# CONTROL_circuit_LED_for_Junction_Box.net
KiCad netlist of a schematic drawn in EAGLE
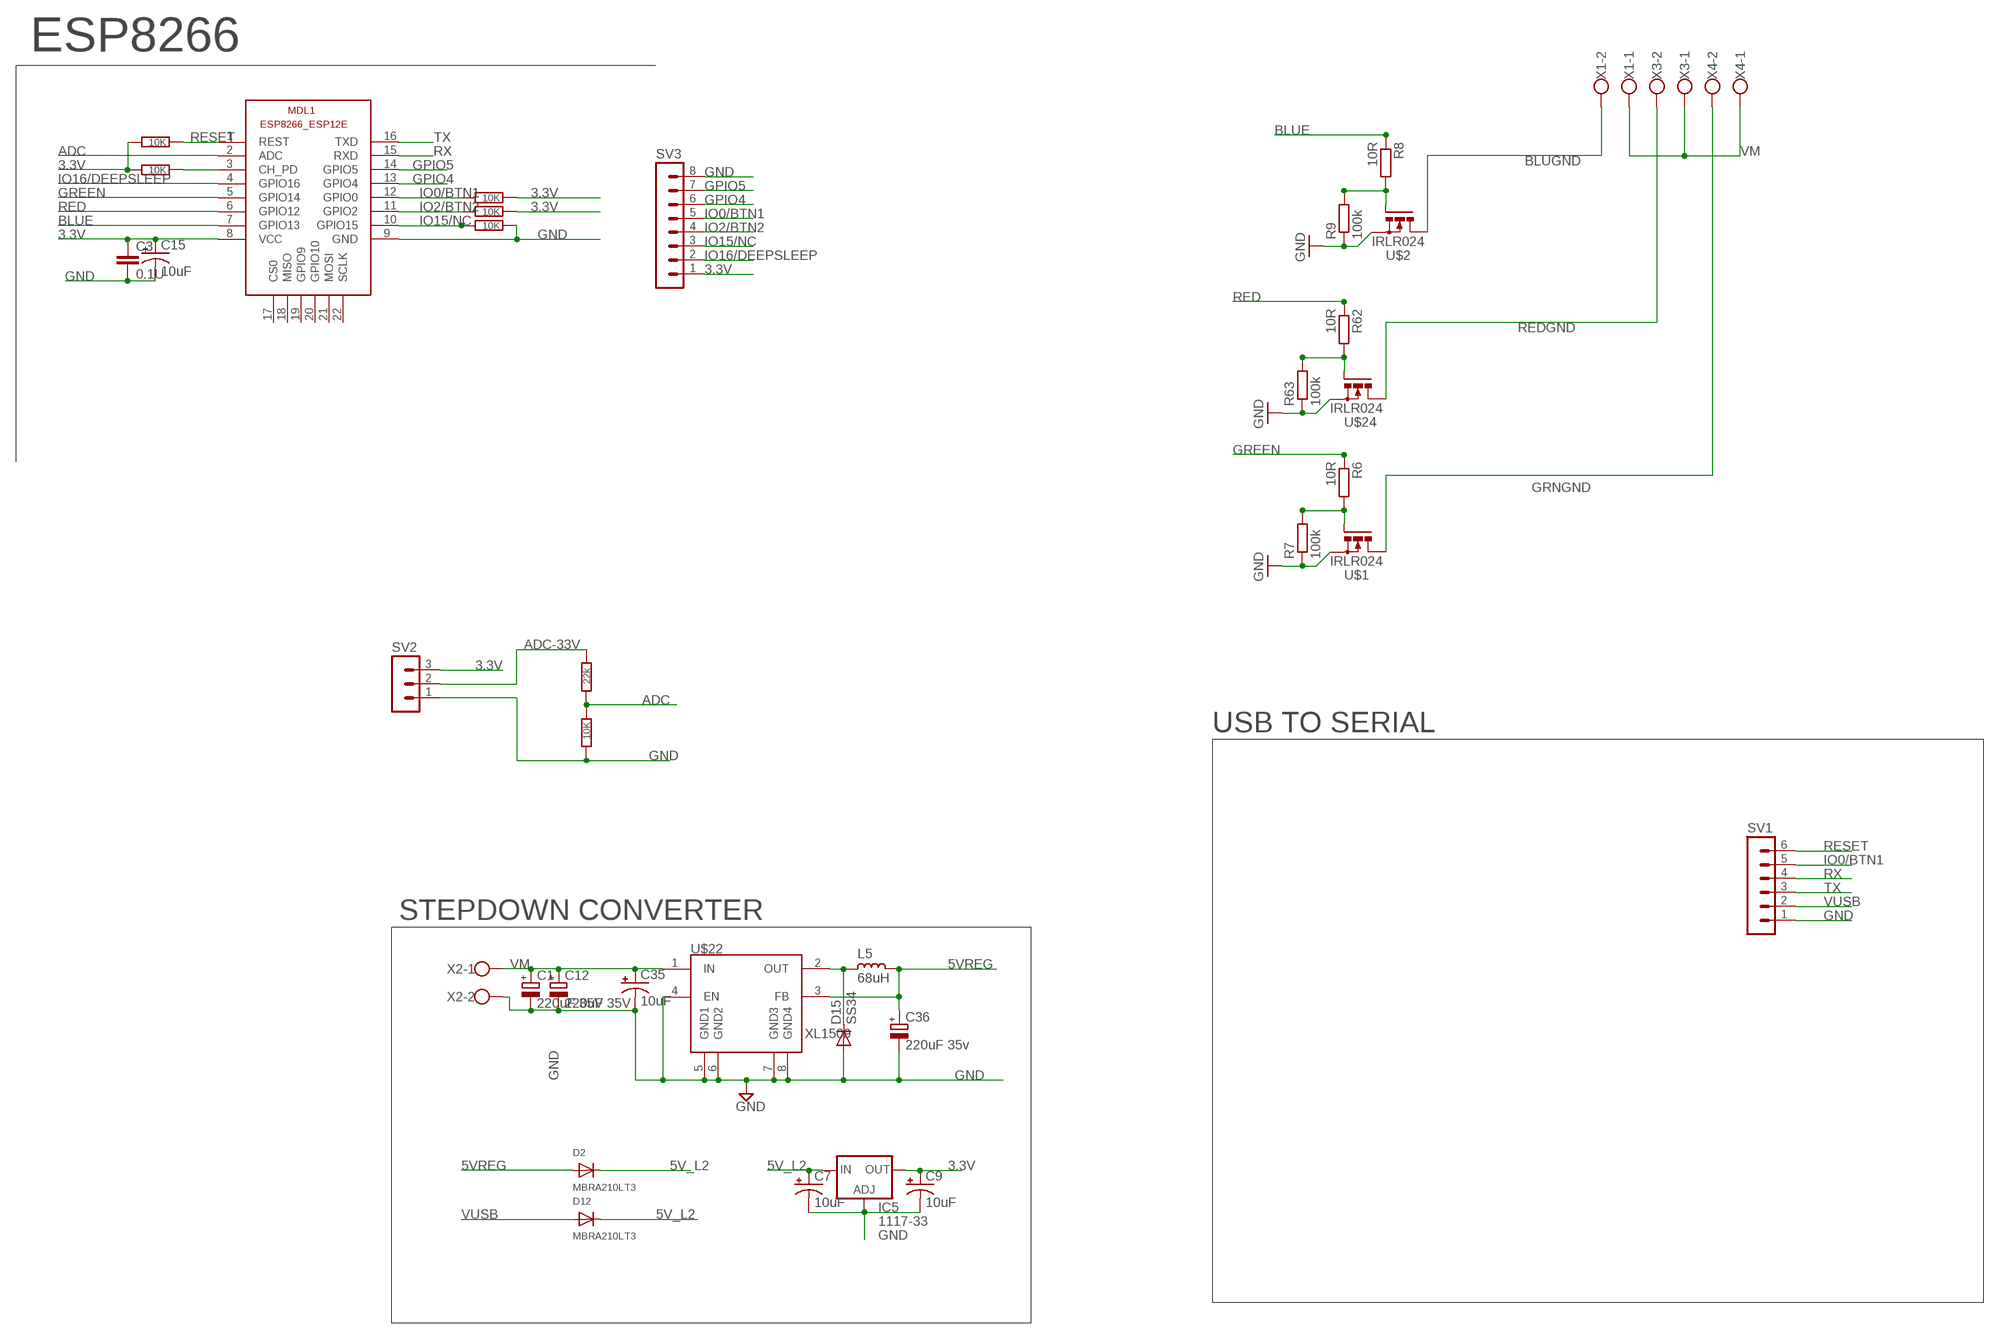
[diagram p0: schematic, sheet 1]

(export (version "E")
  (design (tool "Eeschema 10.0.6"))
  (components
    (comp (ref "C1")
      (value "220uF 35V")
      (footprint "eagle-import:E3,5-8")
      (libsource (lib "eagle-import") (part "CPOL-EUE3.5-8"))
    )
    (comp (ref "C3")
      (value "0.1U")
      (footprint "eagle-import:C1206")
      (libsource (lib "eagle-import") (part "C-EUC1206"))
    )
    (comp (ref "C7")
      (value "10uF")
      (footprint "eagle-import:EIA3216")
      (libsource (lib "eagle-import") (part "CAP_POL1206"))
    )
    (comp (ref "C9")
      (value "10uF")
      (footprint "eagle-import:EIA3216")
      (libsource (lib "eagle-import") (part "CAP_POL1206"))
    )
    (comp (ref "C12")
      (value "220uF 35V")
      (footprint "eagle-import:E3,5-8")
      (libsource (lib "eagle-import") (part "CPOL-EUE3.5-8"))
    )
    (comp (ref "C15")
      (value "10uF")
      (footprint "eagle-import:EIA3216")
      (libsource (lib "eagle-import") (part "CAP_POL1206"))
    )
    (comp (ref "C35")
      (value "10uF")
      (footprint "eagle-import:EIA3216")
      (libsource (lib "eagle-import") (part "CAP_POL1206"))
    )
    (comp (ref "C36")
      (value "220uF 35v")
      (footprint "eagle-import:E3,5-8")
      (libsource (lib "eagle-import") (part "CPOL-EUE3.5-8"))
    )
    (comp (ref "D2")
      (value "MBRA210LT3")
      (footprint "eagle-import:SMADIODE")
      (libsource (lib "eagle-import") (part "DIODESMA"))
    )
    (comp (ref "D12")
      (value "MBRA210LT3")
      (footprint "eagle-import:SMADIODE")
      (libsource (lib "eagle-import") (part "DIODESMA"))
    )
    (comp (ref "D15")
      (value "SS34")
      (footprint "eagle-import:DO-214AC")
      (libsource (lib "eagle-import") (part "DIODE-DO-214AC"))
    )
    (comp (ref "IC5")
      (value "1117-33")
      (footprint "eagle-import:SOT223")
      (libsource (lib "eagle-import") (part "LD117A?S33TR"))
    )
    (comp (ref "L5")
      (value "68uH")
      (footprint "eagle-import:CD75")
      (libsource (lib "eagle-import") (part "L_CD75"))
    )
    (comp (ref "MDL1")
      (value "ESP8266-12EESP8266-ESP12E")
      (footprint "eagle-import:ESP8266-ESP12E")
      (libsource (lib "eagle-import") (part "ESP8266-12EESP8266-ESP12E"))
    )
    (comp (ref "R3")
      (value "22k")
      (footprint "eagle-import:R1206")
      (libsource (lib "eagle-import") (part "R-EU_R1206"))
    )
    (comp (ref "R4")
      (value "10K")
      (footprint "eagle-import:R1206")
      (libsource (lib "eagle-import") (part "R-EU_R1206"))
    )
    (comp (ref "R6")
      (value "10R")
      (footprint "eagle-import:R1206")
      (libsource (lib "eagle-import") (part "resistor_R-EU_R1206"))
    )
    (comp (ref "R7")
      (value "100k")
      (footprint "eagle-import:R1206")
      (libsource (lib "eagle-import") (part "resistor_R-EU_R1206"))
    )
    (comp (ref "R8")
      (value "10R")
      (footprint "eagle-import:R1206")
      (libsource (lib "eagle-import") (part "resistor_R-EU_R1206"))
    )
    (comp (ref "R9")
      (value "100k")
      (footprint "eagle-import:R1206")
      (libsource (lib "eagle-import") (part "resistor_R-EU_R1206"))
    )
    (comp (ref "R11")
      (value "10K")
      (footprint "eagle-import:R1206")
      (libsource (lib "eagle-import") (part "R-EU_R1206"))
    )
    (comp (ref "R12")
      (value "10K")
      (footprint "eagle-import:R1206")
      (libsource (lib "eagle-import") (part "R-EU_R1206"))
    )
    (comp (ref "R28")
      (value "10K")
      (footprint "eagle-import:R1206")
      (libsource (lib "eagle-import") (part "R-EU_R1206"))
    )
    (comp (ref "R29")
      (value "10K")
      (footprint "eagle-import:R1206")
      (libsource (lib "eagle-import") (part "R-EU_R1206"))
    )
    (comp (ref "R31")
      (value "10K")
      (footprint "eagle-import:R1206")
      (libsource (lib "eagle-import") (part "R-EU_R1206"))
    )
    (comp (ref "R62")
      (value "10R")
      (footprint "eagle-import:R1206")
      (libsource (lib "eagle-import") (part "resistor_R-EU_R1206"))
    )
    (comp (ref "R63")
      (value "100k")
      (footprint "eagle-import:R1206")
      (libsource (lib "eagle-import") (part "resistor_R-EU_R1206"))
    )
    (comp (ref "SV1")
      (value "MA06-1")
      (footprint "eagle-import:MA06-1")
      (libsource (lib "eagle-import") (part "MA06-1"))
    )
    (comp (ref "SV2")
      (value "MA03-1")
      (footprint "eagle-import:MA03-1")
      (libsource (lib "eagle-import") (part "MA03-1"))
    )
    (comp (ref "SV3")
      (value "MA08-1")
      (footprint "eagle-import:MA08-1")
      (libsource (lib "eagle-import") (part "MA08-1"))
    )
    (comp (ref "U$1")
      (value "IRLR024")
      (footprint "eagle-import:D-PAK_TO252AA")
      (libsource (lib "eagle-import") (part "N-POWER-MOSFETDPAK-MOSFET"))
    )
    (comp (ref "U$2")
      (value "IRLR024")
      (footprint "eagle-import:D-PAK_TO252AA")
      (libsource (lib "eagle-import") (part "N-POWER-MOSFETDPAK-MOSFET"))
    )
    (comp (ref "U$22")
      (value "XL1509")
      (footprint "eagle-import:SO08")
      (libsource (lib "eagle-import") (part "XL1509"))
    )
    (comp (ref "U$24")
      (value "IRLR024")
      (footprint "eagle-import:D-PAK_TO252AA")
      (libsource (lib "eagle-import") (part "N-POWER-MOSFETDPAK-MOSFET"))
    )
    (comp (ref "X1")
      (value "W237-102")
      (footprint "eagle-import:W237-102")
      (fields (field (name "MPN") "237-102"))
      (libsource (lib "eagle-import") (part "W237-102"))
    )
    (comp (ref "X2")
      (value "W237-102")
      (footprint "eagle-import:W237-102")
      (fields (field (name "MPN") "237-102"))
      (libsource (lib "eagle-import") (part "W237-102"))
    )
    (comp (ref "X3")
      (value "W237-102")
      (footprint "eagle-import:W237-102")
      (fields (field (name "MPN") "237-102"))
      (libsource (lib "eagle-import") (part "W237-102"))
    )
    (comp (ref "X4")
      (value "W237-102")
      (footprint "eagle-import:W237-102")
      (fields (field (name "MPN") "237-102"))
      (libsource (lib "eagle-import") (part "W237-102"))
    )
  )
  (nets
    (net (code "1") (name "/3.3V") (class "Default")
      (node (ref "C15") (pin "A") (pinfunction "+_A") (pintype "passive"))
      (node (ref "C3") (pin "1") (pinfunction "1_1") (pintype "passive"))
      (node (ref "C9") (pin "A") (pinfunction "+_A") (pintype "passive"))
      (node (ref "IC5") (pin "4") (pinfunction "OUT_4") (pintype "passive"))
      (node (ref "MDL1") (pin "8") (pinfunction "VCC_8") (pintype "bidirectional"))
      (node (ref "R11") (pin "2") (pinfunction "2_2") (pintype "passive"))
      (node (ref "R12") (pin "2") (pinfunction "2_2") (pintype "passive"))
      (node (ref "R28") (pin "1") (pinfunction "1_1") (pintype "passive"))
      (node (ref "R29") (pin "1") (pinfunction "1_1") (pintype "passive"))
      (node (ref "SV2") (pin "3") (pinfunction "3_3") (pintype "passive"))
      (node (ref "SV3") (pin "1") (pinfunction "1_1") (pintype "passive"))
    )
    (net (code "2") (name "/5VREG") (class "Default")
      (node (ref "C36") (pin "+") (pinfunction "+_+") (pintype "passive"))
      (node (ref "D2") (pin "A") (pinfunction "A_A") (pintype "passive"))
      (node (ref "L5") (pin "1") (pinfunction "1_1") (pintype "passive"))
      (node (ref "U$22") (pin "3") (pinfunction "FB_3") (pintype "bidirectional"))
    )
    (net (code "3") (name "/5V_L2") (class "Default")
      (node (ref "C7") (pin "A") (pinfunction "+_A") (pintype "passive"))
      (node (ref "D12") (pin "C") (pinfunction "C_C") (pintype "passive"))
      (node (ref "D2") (pin "C") (pinfunction "C_C") (pintype "passive"))
      (node (ref "IC5") (pin "3") (pinfunction "IN_3") (pintype "input"))
    )
    (net (code "4") (name "/ADC") (class "Default")
      (node (ref "MDL1") (pin "2") (pinfunction "ADC_2") (pintype "bidirectional"))
      (node (ref "R3") (pin "1") (pinfunction "1_1") (pintype "passive"))
      (node (ref "R4") (pin "2") (pinfunction "2_2") (pintype "passive"))
    )
    (net (code "5") (name "/ADC-33V") (class "Default")
      (node (ref "R3") (pin "2") (pinfunction "2_2") (pintype "passive"))
      (node (ref "SV2") (pin "2") (pinfunction "2_2") (pintype "passive"))
    )
    (net (code "6") (name "/BLUE") (class "Default")
      (node (ref "MDL1") (pin "7") (pinfunction "GPIO13_7") (pintype "bidirectional"))
      (node (ref "R8") (pin "1") (pinfunction "1_1") (pintype "passive"))
    )
    (net (code "7") (name "/BLUGND") (class "Default")
      (node (ref "U$2") (pin "4") (pinfunction "D_4") (pintype "passive"))
      (node (ref "X1") (pin "2") (pinfunction "KL_2") (pintype "passive"))
    )
    (net (code "8") (name "/GPIO4") (class "Default")
      (node (ref "MDL1") (pin "13") (pinfunction "GPIO4_13") (pintype "bidirectional"))
      (node (ref "SV3") (pin "6") (pinfunction "6_6") (pintype "passive"))
    )
    (net (code "9") (name "/GPIO5") (class "Default")
      (node (ref "MDL1") (pin "14") (pinfunction "GPIO5_14") (pintype "bidirectional"))
      (node (ref "SV3") (pin "7") (pinfunction "7_7") (pintype "passive"))
    )
    (net (code "10") (name "/GREEN") (class "Default")
      (node (ref "MDL1") (pin "5") (pinfunction "GPIO14_5") (pintype "bidirectional"))
      (node (ref "R6") (pin "1") (pinfunction "1_1") (pintype "passive"))
    )
    (net (code "11") (name "/GRNGND") (class "Default")
      (node (ref "U$1") (pin "4") (pinfunction "D_4") (pintype "passive"))
      (node (ref "X4") (pin "2") (pinfunction "KL_2") (pintype "passive"))
    )
    (net (code "12") (name "/IO0{slash}BTN1") (class "Default")
      (node (ref "MDL1") (pin "12") (pinfunction "GPIO0_12") (pintype "bidirectional"))
      (node (ref "R12") (pin "1") (pinfunction "1_1") (pintype "passive"))
      (node (ref "SV1") (pin "5") (pinfunction "5_5") (pintype "passive"))
      (node (ref "SV3") (pin "5") (pinfunction "5_5") (pintype "passive"))
    )
    (net (code "13") (name "/IO2{slash}BTN2") (class "Default")
      (node (ref "MDL1") (pin "11") (pinfunction "GPIO2_11") (pintype "bidirectional"))
      (node (ref "R11") (pin "1") (pinfunction "1_1") (pintype "passive"))
      (node (ref "SV3") (pin "4") (pinfunction "4_4") (pintype "passive"))
    )
    (net (code "14") (name "/IO15{slash}NC") (class "Default")
      (node (ref "MDL1") (pin "10") (pinfunction "GPIO15_10") (pintype "bidirectional"))
      (node (ref "R31") (pin "1") (pinfunction "1_1") (pintype "passive"))
      (node (ref "SV3") (pin "3") (pinfunction "3_3") (pintype "passive"))
    )
    (net (code "15") (name "/IO16{slash}DEEPSLEEP") (class "Default")
      (node (ref "MDL1") (pin "4") (pinfunction "GPIO16_4") (pintype "bidirectional"))
      (node (ref "SV3") (pin "2") (pinfunction "2_2") (pintype "passive"))
    )
    (net (code "16") (name "/RED") (class "Default")
      (node (ref "MDL1") (pin "6") (pinfunction "GPIO12_6") (pintype "bidirectional"))
      (node (ref "R62") (pin "1") (pinfunction "1_1") (pintype "passive"))
    )
    (net (code "17") (name "/REDGND") (class "Default")
      (node (ref "U$24") (pin "4") (pinfunction "D_4") (pintype "passive"))
      (node (ref "X3") (pin "2") (pinfunction "KL_2") (pintype "passive"))
    )
    (net (code "18") (name "/RESET") (class "Default")
      (node (ref "MDL1") (pin "1") (pinfunction "REST_1") (pintype "bidirectional"))
      (node (ref "R29") (pin "2") (pinfunction "2_2") (pintype "passive"))
      (node (ref "SV1") (pin "6") (pinfunction "6_6") (pintype "passive"))
    )
    (net (code "19") (name "/RX") (class "Default")
      (node (ref "MDL1") (pin "15") (pinfunction "RXD_15") (pintype "bidirectional"))
      (node (ref "SV1") (pin "4") (pinfunction "4_4") (pintype "passive"))
    )
    (net (code "20") (name "/TX") (class "Default")
      (node (ref "MDL1") (pin "16") (pinfunction "TXD_16") (pintype "bidirectional"))
      (node (ref "SV1") (pin "3") (pinfunction "3_3") (pintype "passive"))
    )
    (net (code "21") (name "/VM") (class "Default")
      (node (ref "C1") (pin "+") (pinfunction "+_+") (pintype "passive"))
      (node (ref "C12") (pin "+") (pinfunction "+_+") (pintype "passive"))
      (node (ref "C35") (pin "A") (pinfunction "+_A") (pintype "passive"))
      (node (ref "U$22") (pin "1") (pinfunction "IN_1") (pintype "bidirectional"))
      (node (ref "X1") (pin "1") (pinfunction "KL_1") (pintype "passive"))
      (node (ref "X2") (pin "1") (pinfunction "KL_1") (pintype "passive"))
      (node (ref "X3") (pin "1") (pinfunction "KL_1") (pintype "passive"))
      (node (ref "X4") (pin "1") (pinfunction "KL_1") (pintype "passive"))
    )
    (net (code "22") (name "/VUSB") (class "Default")
      (node (ref "D12") (pin "A") (pinfunction "A_A") (pintype "passive"))
      (node (ref "SV1") (pin "2") (pinfunction "2_2") (pintype "passive"))
    )
    (net (code "23") (name "GND") (class "Default")
      (node (ref "C1") (pin "-") (pinfunction "-_-") (pintype "passive"))
      (node (ref "C12") (pin "-") (pinfunction "-_-") (pintype "passive"))
      (node (ref "C15") (pin "C") (pinfunction "-_C") (pintype "passive"))
      (node (ref "C3") (pin "2") (pinfunction "2_2") (pintype "passive"))
      (node (ref "C35") (pin "C") (pinfunction "-_C") (pintype "passive"))
      (node (ref "C36") (pin "-") (pinfunction "-_-") (pintype "passive"))
      (node (ref "C7") (pin "C") (pinfunction "-_C") (pintype "passive"))
      (node (ref "C9") (pin "C") (pinfunction "-_C") (pintype "passive"))
      (node (ref "D15") (pin "2") (pinfunction "A_2") (pintype "passive"))
      (node (ref "IC5") (pin "1") (pinfunction "ADJ_1") (pintype "input"))
      (node (ref "MDL1") (pin "9") (pinfunction "GND_9") (pintype "bidirectional"))
      (node (ref "R31") (pin "2") (pinfunction "2_2") (pintype "passive"))
      (node (ref "R4") (pin "1") (pinfunction "1_1") (pintype "passive"))
      (node (ref "R63") (pin "1") (pinfunction "1_1") (pintype "passive"))
      (node (ref "R7") (pin "1") (pinfunction "1_1") (pintype "passive"))
      (node (ref "R9") (pin "1") (pinfunction "1_1") (pintype "passive"))
      (node (ref "SV1") (pin "1") (pinfunction "1_1") (pintype "passive"))
      (node (ref "SV2") (pin "1") (pinfunction "1_1") (pintype "passive"))
      (node (ref "SV3") (pin "8") (pinfunction "8_8") (pintype "passive"))
      (node (ref "U$1") (pin "3") (pinfunction "S_3") (pintype "passive"))
      (node (ref "U$2") (pin "3") (pinfunction "S_3") (pintype "passive"))
      (node (ref "U$22") (pin "4") (pinfunction "EN_4") (pintype "bidirectional"))
      (node (ref "U$22") (pin "5") (pinfunction "GND1_5") (pintype "bidirectional"))
      (node (ref "U$22") (pin "6") (pinfunction "GND2_6") (pintype "bidirectional"))
      (node (ref "U$22") (pin "7") (pinfunction "GND3_7") (pintype "bidirectional"))
      (node (ref "U$22") (pin "8") (pinfunction "GND4_8") (pintype "bidirectional"))
      (node (ref "U$24") (pin "3") (pinfunction "S_3") (pintype "passive"))
      (node (ref "X2") (pin "2") (pinfunction "KL_2") (pintype "passive"))
    )
    (net (code "24") (name "Net-(D15-C)") (class "Default")
      (node (ref "D15") (pin "1") (pinfunction "C_1") (pintype "passive"))
      (node (ref "L5") (pin "2") (pinfunction "2_2") (pintype "passive"))
      (node (ref "U$22") (pin "2") (pinfunction "OUT_2") (pintype "bidirectional"))
    )
    (net (code "25") (name "Net-(MDL1-CH_PD)") (class "Default")
      (node (ref "MDL1") (pin "3") (pinfunction "CH_PD_3") (pintype "bidirectional"))
      (node (ref "R28") (pin "2") (pinfunction "2_2") (pintype "passive"))
    )
    (net (code "26") (name "Net-(U$1-G)") (class "Default")
      (node (ref "R6") (pin "2") (pinfunction "2_2") (pintype "passive"))
      (node (ref "R7") (pin "2") (pinfunction "2_2") (pintype "passive"))
      (node (ref "U$1") (pin "1") (pinfunction "G_1") (pintype "passive"))
    )
    (net (code "27") (name "Net-(U$2-G)") (class "Default")
      (node (ref "R8") (pin "2") (pinfunction "2_2") (pintype "passive"))
      (node (ref "R9") (pin "2") (pinfunction "2_2") (pintype "passive"))
      (node (ref "U$2") (pin "1") (pinfunction "G_1") (pintype "passive"))
    )
    (net (code "28") (name "Net-(U$24-G)") (class "Default")
      (node (ref "R62") (pin "2") (pinfunction "2_2") (pintype "passive"))
      (node (ref "R63") (pin "2") (pinfunction "2_2") (pintype "passive"))
      (node (ref "U$24") (pin "1") (pinfunction "G_1") (pintype "passive"))
    )
    (net (code "29") (name "unconnected-(MDL1-CS0-Pad17)") (class "Default")
      (node (ref "MDL1") (pin "17") (pinfunction "CS0_17") (pintype "bidirectional"))
    )
    (net (code "30") (name "unconnected-(MDL1-GPIO9-Pad19)") (class "Default")
      (node (ref "MDL1") (pin "19") (pinfunction "GPIO9_19") (pintype "bidirectional"))
    )
    (net (code "31") (name "unconnected-(MDL1-GPIO10-Pad20)") (class "Default")
      (node (ref "MDL1") (pin "20") (pinfunction "GPIO10_20") (pintype "bidirectional"))
    )
    (net (code "32") (name "unconnected-(MDL1-MISO-Pad18)") (class "Default")
      (node (ref "MDL1") (pin "18") (pinfunction "MISO_18") (pintype "bidirectional"))
    )
    (net (code "33") (name "unconnected-(MDL1-MOSI-Pad21)") (class "Default")
      (node (ref "MDL1") (pin "21") (pinfunction "MOSI_21") (pintype "bidirectional"))
    )
    (net (code "34") (name "unconnected-(MDL1-SCLK-Pad22)") (class "Default")
      (node (ref "MDL1") (pin "22") (pinfunction "SCLK_22") (pintype "bidirectional"))
    )
  )
)
